# PCB_LC_LPF-16-20.net
KiCad netlist of a schematic drawn in Altium Designer
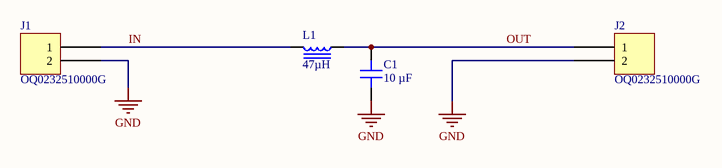
[diagram p0: PCB_LC_LPF-16-20.SchDoc]

(export (version "E")
  (design (tool "Eeschema 10.0.6"))
  (components
    (comp (ref "C1")
      (value "10 µF")
      (footprint "CAP 0603_1608")
      (description "CAP CER 10UF 10V X5R 0603")
      (fields
        (field (name "PART NUMBER") "MD0603BW106M100NHT-EM")
        (field (name "MANUFACTURER") "Knowles Novacap")
      )
      (libsource (lib "Celestial Altium Library - altium_library") (part "Capacitor"))
    )
    (comp (ref "J1")
      (value "OQ0232510000G")
      (footprint "FCI 06-381-2PIN")
      (description "TERM BLOCK HDR 2POS 90DEG 3.81MM")
      (fields (field (name "MANUFACTURER") "Amphenol Anytek"))
      (libsource (lib "Celestial Altium Library - altium_library") (part "2 Pin"))
    )
    (comp (ref "J2")
      (value "OQ0232510000G")
      (footprint "FCI 06-381-2PIN")
      (description "TERM BLOCK HDR 2POS 90DEG 3.81MM")
      (fields (field (name "MANUFACTURER") "Amphenol Anytek"))
      (libsource (lib "") (part "2 Pin_1"))
    )
    (comp (ref "L1")
      (value "47µH")
      (footprint "IND 0603_1608 RF WW")
      (description "INDUCTORPOWER LINE 0603 47H 20%")
      (fields (field (name "PART NUMBER") "L0603B470MPWFT") (field (name "MANUFACTURER") "KEMET"))
      (libsource (lib "Celestial Altium Library - altium_library") (part "Inductor"))
    )
  )
  (nets
    (net (code "1") (name "/IN") (class "Default")
      (node (ref "J1") (pin "1") (pinfunction "1_1") (pintype "passive"))
      (node (ref "L1") (pin "2") (pinfunction "2_2") (pintype "passive"))
    )
    (net (code "2") (name "/OUT") (class "Default")
      (node (ref "C1") (pin "2") (pinfunction "2_2") (pintype "passive"))
      (node (ref "J2") (pin "1") (pinfunction "1_1") (pintype "passive"))
      (node (ref "L1") (pin "1") (pinfunction "1_1") (pintype "passive"))
    )
    (net (code "3") (name "GND") (class "Default")
      (node (ref "C1") (pin "1") (pinfunction "1_1") (pintype "passive"))
      (node (ref "J1") (pin "2") (pinfunction "2_2") (pintype "passive"))
      (node (ref "J2") (pin "2") (pinfunction "2_2") (pintype "passive"))
    )
  )
)
